# variable.net
KiCad netlist of a schematic drawn in EAGLE
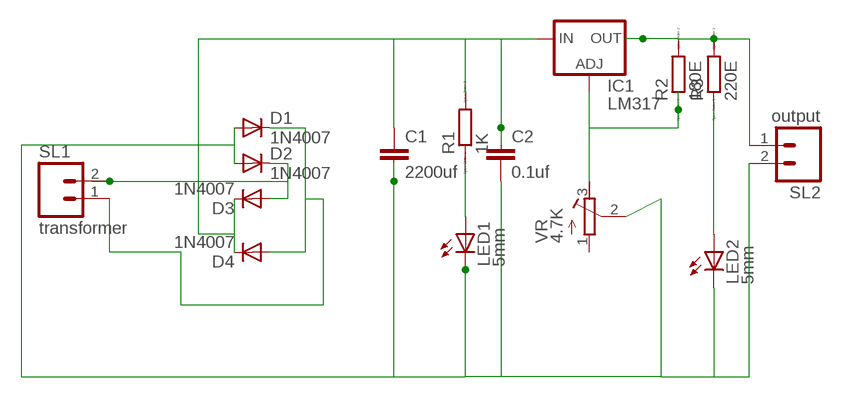
[diagram p0: schematic, sheet 1]

(export (version "E")
  (design (tool "Eeschema 10.0.6"))
  (components
    (comp (ref "C1")
      (value "2200uf")
      (footprint "eagle-import:C5B7.2")
      (libsource (lib "eagle-import") (part "C5/7.2"))
    )
    (comp (ref "C2")
      (value "0.1uf")
      (footprint "eagle-import:C2.5-2")
      (libsource (lib "eagle-import") (part "C2.5/2"))
    )
    (comp (ref "D1")
      (value "1N4007")
      (footprint "eagle-import:DO41-10")
      (libsource (lib "eagle-import") (part "1N4004"))
    )
    (comp (ref "D2")
      (value "1N4007")
      (footprint "eagle-import:DO41-10")
      (libsource (lib "eagle-import") (part "1N4004"))
    )
    (comp (ref "D3")
      (value "1N4007")
      (footprint "eagle-import:DO41-10")
      (libsource (lib "eagle-import") (part "1N4004"))
    )
    (comp (ref "D4")
      (value "1N4007")
      (footprint "eagle-import:DO41-10")
      (libsource (lib "eagle-import") (part "1N4004"))
    )
    (comp (ref "IC1")
      (value "LM317")
      (footprint "eagle-import:317TL")
      (libsource (lib "eagle-import") (part "LM317TL"))
    )
    (comp (ref "LED1")
      (value "5mm")
      (footprint "eagle-import:LED5MM")
      (libsource (lib "eagle-import") (part "LED5MM"))
    )
    (comp (ref "LED2")
      (value "5mm")
      (footprint "eagle-import:LED5MM")
      (libsource (lib "eagle-import") (part "LED5MM"))
    )
    (comp (ref "R1")
      (value "1K")
      (footprint "eagle-import:0204_7")
      (libsource (lib "eagle-import") (part "R0204/7"))
    )
    (comp (ref "R2")
      (value "180E")
      (footprint "eagle-import:0204_7")
      (libsource (lib "eagle-import") (part "R0204/7"))
    )
    (comp (ref "R3")
      (value "220E")
      (footprint "eagle-import:0204_7")
      (libsource (lib "eagle-import") (part "R0204/7"))
    )
    (comp (ref "SL1")
      (value "transformer")
      (footprint "eagle-import:02P")
      (libsource (lib "eagle-import") (part "M02"))
    )
    (comp (ref "SL2")
      (value "output")
      (footprint "eagle-import:02P")
      (libsource (lib "eagle-import") (part "M02"))
    )
    (comp (ref "VR")
      (value "4.7K")
      (footprint "eagle-import:RTRIM64P")
      (libsource (lib "eagle-import") (part "R-TRIMM64P"))
    )
  )
  (nets
    (net (code "1") (name "Net-(D1-PadC)") (class "Default")
      (node (ref "D1") (pin "C") (pinfunction "C_C") (pintype "passive"))
      (node (ref "D4") (pin "A") (pinfunction "A_A") (pintype "passive"))
      (node (ref "SL1") (pin "1") (pinfunction "1_1") (pintype "passive"))
    )
    (net (code "2") (name "Net-(D2-PadC)") (class "Default")
      (node (ref "D2") (pin "C") (pinfunction "C_C") (pintype "passive"))
      (node (ref "D3") (pin "A") (pinfunction "A_A") (pintype "passive"))
      (node (ref "SL1") (pin "2") (pinfunction "2_2") (pintype "passive"))
    )
    (net (code "3") (name "Net-(IC1-ADJ)") (class "Default")
      (node (ref "IC1") (pin "1") (pinfunction "ADJ_1") (pintype "input"))
      (node (ref "R2") (pin "1") (pinfunction "1_1") (pintype "passive"))
      (node (ref "VR") (pin "3") (pinfunction "A_3") (pintype "passive"))
    )
    (net (code "4") (name "Net-(IC1-IN)") (class "Default")
      (node (ref "C1") (pin "1") (pinfunction "1_1") (pintype "passive"))
      (node (ref "C2") (pin "1") (pinfunction "1_1") (pintype "passive"))
      (node (ref "D3") (pin "C") (pinfunction "C_C") (pintype "passive"))
      (node (ref "D4") (pin "C") (pinfunction "C_C") (pintype "passive"))
      (node (ref "IC1") (pin "3") (pinfunction "IN_3") (pintype "input"))
      (node (ref "R1") (pin "2") (pinfunction "2_2") (pintype "passive"))
    )
    (net (code "5") (name "Net-(IC1-OUT)") (class "Default")
      (node (ref "IC1") (pin "2") (pinfunction "OUT_2") (pintype "passive"))
      (node (ref "R2") (pin "2") (pinfunction "2_2") (pintype "passive"))
      (node (ref "R3") (pin "2") (pinfunction "2_2") (pintype "passive"))
      (node (ref "SL2") (pin "1") (pinfunction "1_1") (pintype "passive"))
    )
    (net (code "6") (name "Net-(LED1-C)") (class "Default")
      (node (ref "C1") (pin "2") (pinfunction "2_2") (pintype "passive"))
      (node (ref "C2") (pin "2") (pinfunction "2_2") (pintype "passive"))
      (node (ref "D1") (pin "A") (pinfunction "A_A") (pintype "passive"))
      (node (ref "D2") (pin "A") (pinfunction "A_A") (pintype "passive"))
      (node (ref "LED1") (pin "K") (pinfunction "C_K") (pintype "passive"))
      (node (ref "LED2") (pin "K") (pinfunction "C_K") (pintype "passive"))
      (node (ref "SL2") (pin "2") (pinfunction "2_2") (pintype "passive"))
      (node (ref "VR") (pin "2") (pinfunction "S_2") (pintype "passive"))
    )
    (net (code "7") (name "Net-(LED1-PadA)") (class "Default")
      (node (ref "LED1") (pin "A") (pinfunction "A_A") (pintype "passive"))
      (node (ref "R1") (pin "1") (pinfunction "1_1") (pintype "passive"))
    )
    (net (code "8") (name "Net-(LED2-PadA)") (class "Default")
      (node (ref "LED2") (pin "A") (pinfunction "A_A") (pintype "passive"))
      (node (ref "R3") (pin "1") (pinfunction "1_1") (pintype "passive"))
    )
    (net (code "9") (name "unconnected-(VR-E-Pad1)") (class "Default")
      (node (ref "VR") (pin "1") (pinfunction "E_1") (pintype "passive"))
    )
  )
)
